# node_sound.net
KiCad netlist of a schematic drawn in EAGLE
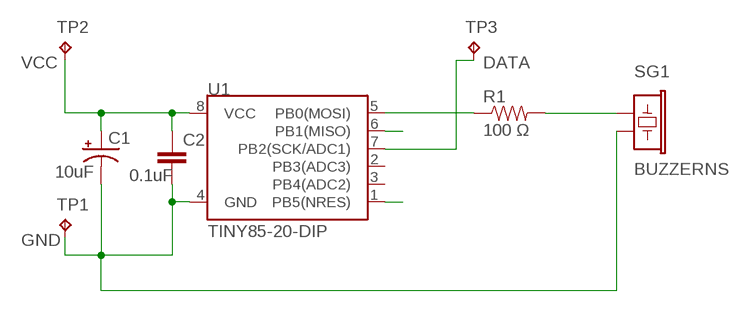
[diagram p0: schematic, sheet 1]

(export (version "E")
  (design (tool "Eeschema 10.0.6"))
  (components
    (comp (ref "C1")
      (value "10uF")
      (footprint "eagle-import:EIA3216")
      (libsource (lib "eagle-import") (part "10UF-16V-10%(TANT)"))
    )
    (comp (ref "C2")
      (value "0.1uF")
      (footprint "eagle-import:1206")
      (libsource (lib "eagle-import") (part "CAP1206"))
    )
    (comp (ref "R1")
      (value "100 Ω")
      (footprint "eagle-import:1206")
      (libsource (lib "eagle-import") (part "RESISTOR1206"))
    )
    (comp (ref "SG1")
      (value "BUZZERNS")
      (footprint "eagle-import:BUZZER-12MM-NS")
      (libsource (lib "eagle-import") (part "BUZZERNS"))
    )
    (comp (ref "TP1")
      (value "PADSTP13R")
      (footprint "eagle-import:CIRCLE-PAD-1_4")
      (fields (field (name "TP_SIGNAL_NAME") "GND"))
      (libsource (lib "eagle-import") (part "PADSTP13R"))
    )
    (comp (ref "TP2")
      (value "PADSTP13R")
      (footprint "eagle-import:CIRCLE-PAD-1_4")
      (fields (field (name "TP_SIGNAL_NAME") "VCC"))
      (libsource (lib "eagle-import") (part "PADSTP13R"))
    )
    (comp (ref "TP3")
      (value "PADSTP13R")
      (footprint "eagle-import:CIRCLE-PAD-1_4")
      (fields (field (name "TP_SIGNAL_NAME") "DATA"))
      (libsource (lib "eagle-import") (part "PADSTP13R"))
    )
    (comp (ref "U1")
      (value "TINY85-20-DIP")
      (footprint "eagle-import:DIP08")
      (libsource (lib "eagle-import") (part "ATTINY45TINY45-20-DIP"))
    )
  )
  (nets
    (net (code "1") (name "Net-(C1-+)") (class "Default")
      (node (ref "C1") (pin "A") (pinfunction "+_A") (pintype "passive"))
      (node (ref "C2") (pin "1") (pinfunction "1_1") (pintype "passive"))
      (node (ref "TP2") (pin "TP") (pinfunction "TP_TP") (pintype "input"))
      (node (ref "U1") (pin "8") (pinfunction "VCC_8") (pintype "bidirectional"))
    )
    (net (code "2") (name "Net-(C1--)") (class "Default")
      (node (ref "C1") (pin "C") (pinfunction "-_C") (pintype "passive"))
      (node (ref "C2") (pin "2") (pinfunction "2_2") (pintype "passive"))
      (node (ref "SG1") (pin "-") (pinfunction "2_-") (pintype "passive"))
      (node (ref "TP1") (pin "TP") (pinfunction "TP_TP") (pintype "input"))
      (node (ref "U1") (pin "4") (pinfunction "GND_4") (pintype "bidirectional"))
    )
    (net (code "3") (name "Net-(SG1-1)") (class "Default")
      (node (ref "R1") (pin "2") (pinfunction "2_2") (pintype "passive"))
      (node (ref "SG1") (pin "+") (pinfunction "1_+") (pintype "passive"))
    )
    (net (code "4") (name "Net-(U1-PB0(MOSI))") (class "Default")
      (node (ref "R1") (pin "1") (pinfunction "1_1") (pintype "passive"))
      (node (ref "U1") (pin "5") (pinfunction "PB0(MOSI)_5") (pintype "bidirectional"))
    )
    (net (code "5") (name "Net-(U1-PB2(SCK{slash}ADC1))") (class "Default")
      (node (ref "TP3") (pin "TP") (pinfunction "TP_TP") (pintype "input"))
      (node (ref "U1") (pin "7") (pinfunction "PB2(SCK/ADC1)_7") (pintype "bidirectional"))
    )
    (net (code "6") (name "unconnected-(U1-PB1(MISO)-Pad6)") (class "Default")
      (node (ref "U1") (pin "6") (pinfunction "PB1(MISO)_6") (pintype "bidirectional"))
    )
    (net (code "7") (name "unconnected-(U1-PB3(ADC3)-Pad2)") (class "Default")
      (node (ref "U1") (pin "2") (pinfunction "PB3(ADC3)_2") (pintype "bidirectional"))
    )
    (net (code "8") (name "unconnected-(U1-PB4(ADC2)-Pad3)") (class "Default")
      (node (ref "U1") (pin "3") (pinfunction "PB4(ADC2)_3") (pintype "bidirectional"))
    )
    (net (code "9") (name "unconnected-(U1-PB5(NRES)-Pad1)") (class "Default")
      (node (ref "U1") (pin "1") (pinfunction "PB5(NRES)_1") (pintype "bidirectional"))
    )
  )
)
